# automatic_light_switch.net
KiCad netlist of a schematic drawn in EAGLE
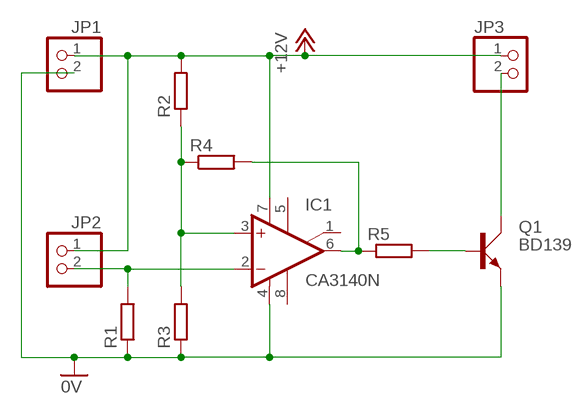
[diagram p0: schematic, sheet 1]

(export (version "E")
  (design (tool "Eeschema 10.0.6"))
  (components
    (comp (ref "IC1")
      (value "CA3140N")
      (footprint "eagle-import:DIL08")
      (libsource (lib "eagle-import") (part "CA3140N"))
    )
    (comp (ref "JP1")
      (value "PINHD-1X2")
      (footprint "eagle-import:1X02")
      (libsource (lib "eagle-import") (part "PINHD-1X2"))
    )
    (comp (ref "JP2")
      (value "PINHD-1X2")
      (footprint "eagle-import:1X02")
      (libsource (lib "eagle-import") (part "PINHD-1X2"))
    )
    (comp (ref "JP3")
      (value "PINHD-1X2")
      (footprint "eagle-import:1X02")
      (libsource (lib "eagle-import") (part "PINHD-1X2"))
    )
    (comp (ref "Q1")
      (value "BD139")
      (footprint "eagle-import:TO126AV")
      (libsource (lib "eagle-import") (part "BD139"))
    )
    (comp (ref "R1")
      (value "R-EU_0207/15")
      (footprint "eagle-import:0207_15")
      (libsource (lib "eagle-import") (part "R-EU_0207/15"))
    )
    (comp (ref "R2")
      (value "R-EU_0207/15")
      (footprint "eagle-import:0207_15")
      (libsource (lib "eagle-import") (part "R-EU_0207/15"))
    )
    (comp (ref "R3")
      (value "R-EU_0207/15")
      (footprint "eagle-import:0207_15")
      (libsource (lib "eagle-import") (part "R-EU_0207/15"))
    )
    (comp (ref "R4")
      (value "R-EU_0207/15")
      (footprint "eagle-import:0207_15")
      (libsource (lib "eagle-import") (part "R-EU_0207/15"))
    )
    (comp (ref "R5")
      (value "R-EU_0207/15")
      (footprint "eagle-import:0207_15")
      (libsource (lib "eagle-import") (part "R-EU_0207/15"))
    )
  )
  (nets
    (net (code "1") (name "+12V") (class "Default")
      (node (ref "IC1") (pin "7") (pinfunction "V+_7") (pintype "power_in"))
      (node (ref "JP1") (pin "1") (pinfunction "1_1") (pintype "passive"))
      (node (ref "JP2") (pin "1") (pinfunction "1_1") (pintype "passive"))
      (node (ref "JP3") (pin "1") (pinfunction "1_1") (pintype "passive"))
      (node (ref "R2") (pin "2") (pinfunction "2_2") (pintype "passive"))
    )
    (net (code "2") (name "0V") (class "Default")
      (node (ref "IC1") (pin "4") (pinfunction "V-_4") (pintype "power_in"))
      (node (ref "JP1") (pin "2") (pinfunction "2_2") (pintype "passive"))
      (node (ref "Q1") (pin "E") (pinfunction "E_E") (pintype "passive"))
      (node (ref "R1") (pin "1") (pinfunction "1_1") (pintype "passive"))
      (node (ref "R3") (pin "1") (pinfunction "1_1") (pintype "passive"))
    )
    (net (code "3") (name "Net-(IC1-+IN)") (class "Default")
      (node (ref "IC1") (pin "3") (pinfunction "+IN_3") (pintype "input"))
      (node (ref "R2") (pin "1") (pinfunction "1_1") (pintype "passive"))
      (node (ref "R3") (pin "2") (pinfunction "2_2") (pintype "passive"))
      (node (ref "R4") (pin "1") (pinfunction "1_1") (pintype "passive"))
    )
    (net (code "4") (name "Net-(IC1--IN)") (class "Default")
      (node (ref "IC1") (pin "2") (pinfunction "-IN_2") (pintype "input"))
      (node (ref "JP2") (pin "2") (pinfunction "2_2") (pintype "passive"))
      (node (ref "R1") (pin "2") (pinfunction "2_2") (pintype "passive"))
    )
    (net (code "5") (name "Net-(IC1-OUT)") (class "Default")
      (node (ref "IC1") (pin "6") (pinfunction "OUT_6") (pintype "output"))
      (node (ref "R4") (pin "2") (pinfunction "2_2") (pintype "passive"))
      (node (ref "R5") (pin "1") (pinfunction "1_1") (pintype "passive"))
    )
    (net (code "6") (name "Net-(JP3-Pad2)") (class "Default")
      (node (ref "JP3") (pin "2") (pinfunction "2_2") (pintype "passive"))
      (node (ref "Q1") (pin "C") (pinfunction "C_C") (pintype "passive"))
    )
    (net (code "7") (name "Net-(Q1-PadB)") (class "Default")
      (node (ref "Q1") (pin "B") (pinfunction "B_B") (pintype "passive"))
      (node (ref "R5") (pin "2") (pinfunction "2_2") (pintype "passive"))
    )
    (net (code "8") (name "unconnected-(IC1-CMP-Pad8)") (class "Default")
      (node (ref "IC1") (pin "8") (pinfunction "CMP_8") (pintype "passive"))
    )
    (net (code "9") (name "unconnected-(IC1-ON-Pad5)") (class "Default")
      (node (ref "IC1") (pin "5") (pinfunction "ON_5") (pintype "passive"))
    )
    (net (code "10") (name "unconnected-(IC1-ON{slash}CMP-Pad1)") (class "Default")
      (node (ref "IC1") (pin "1") (pinfunction "ON/CMP_1") (pintype "passive"))
    )
  )
)
